# Sheet1.net
KiCad netlist of a schematic drawn in Altium Designer
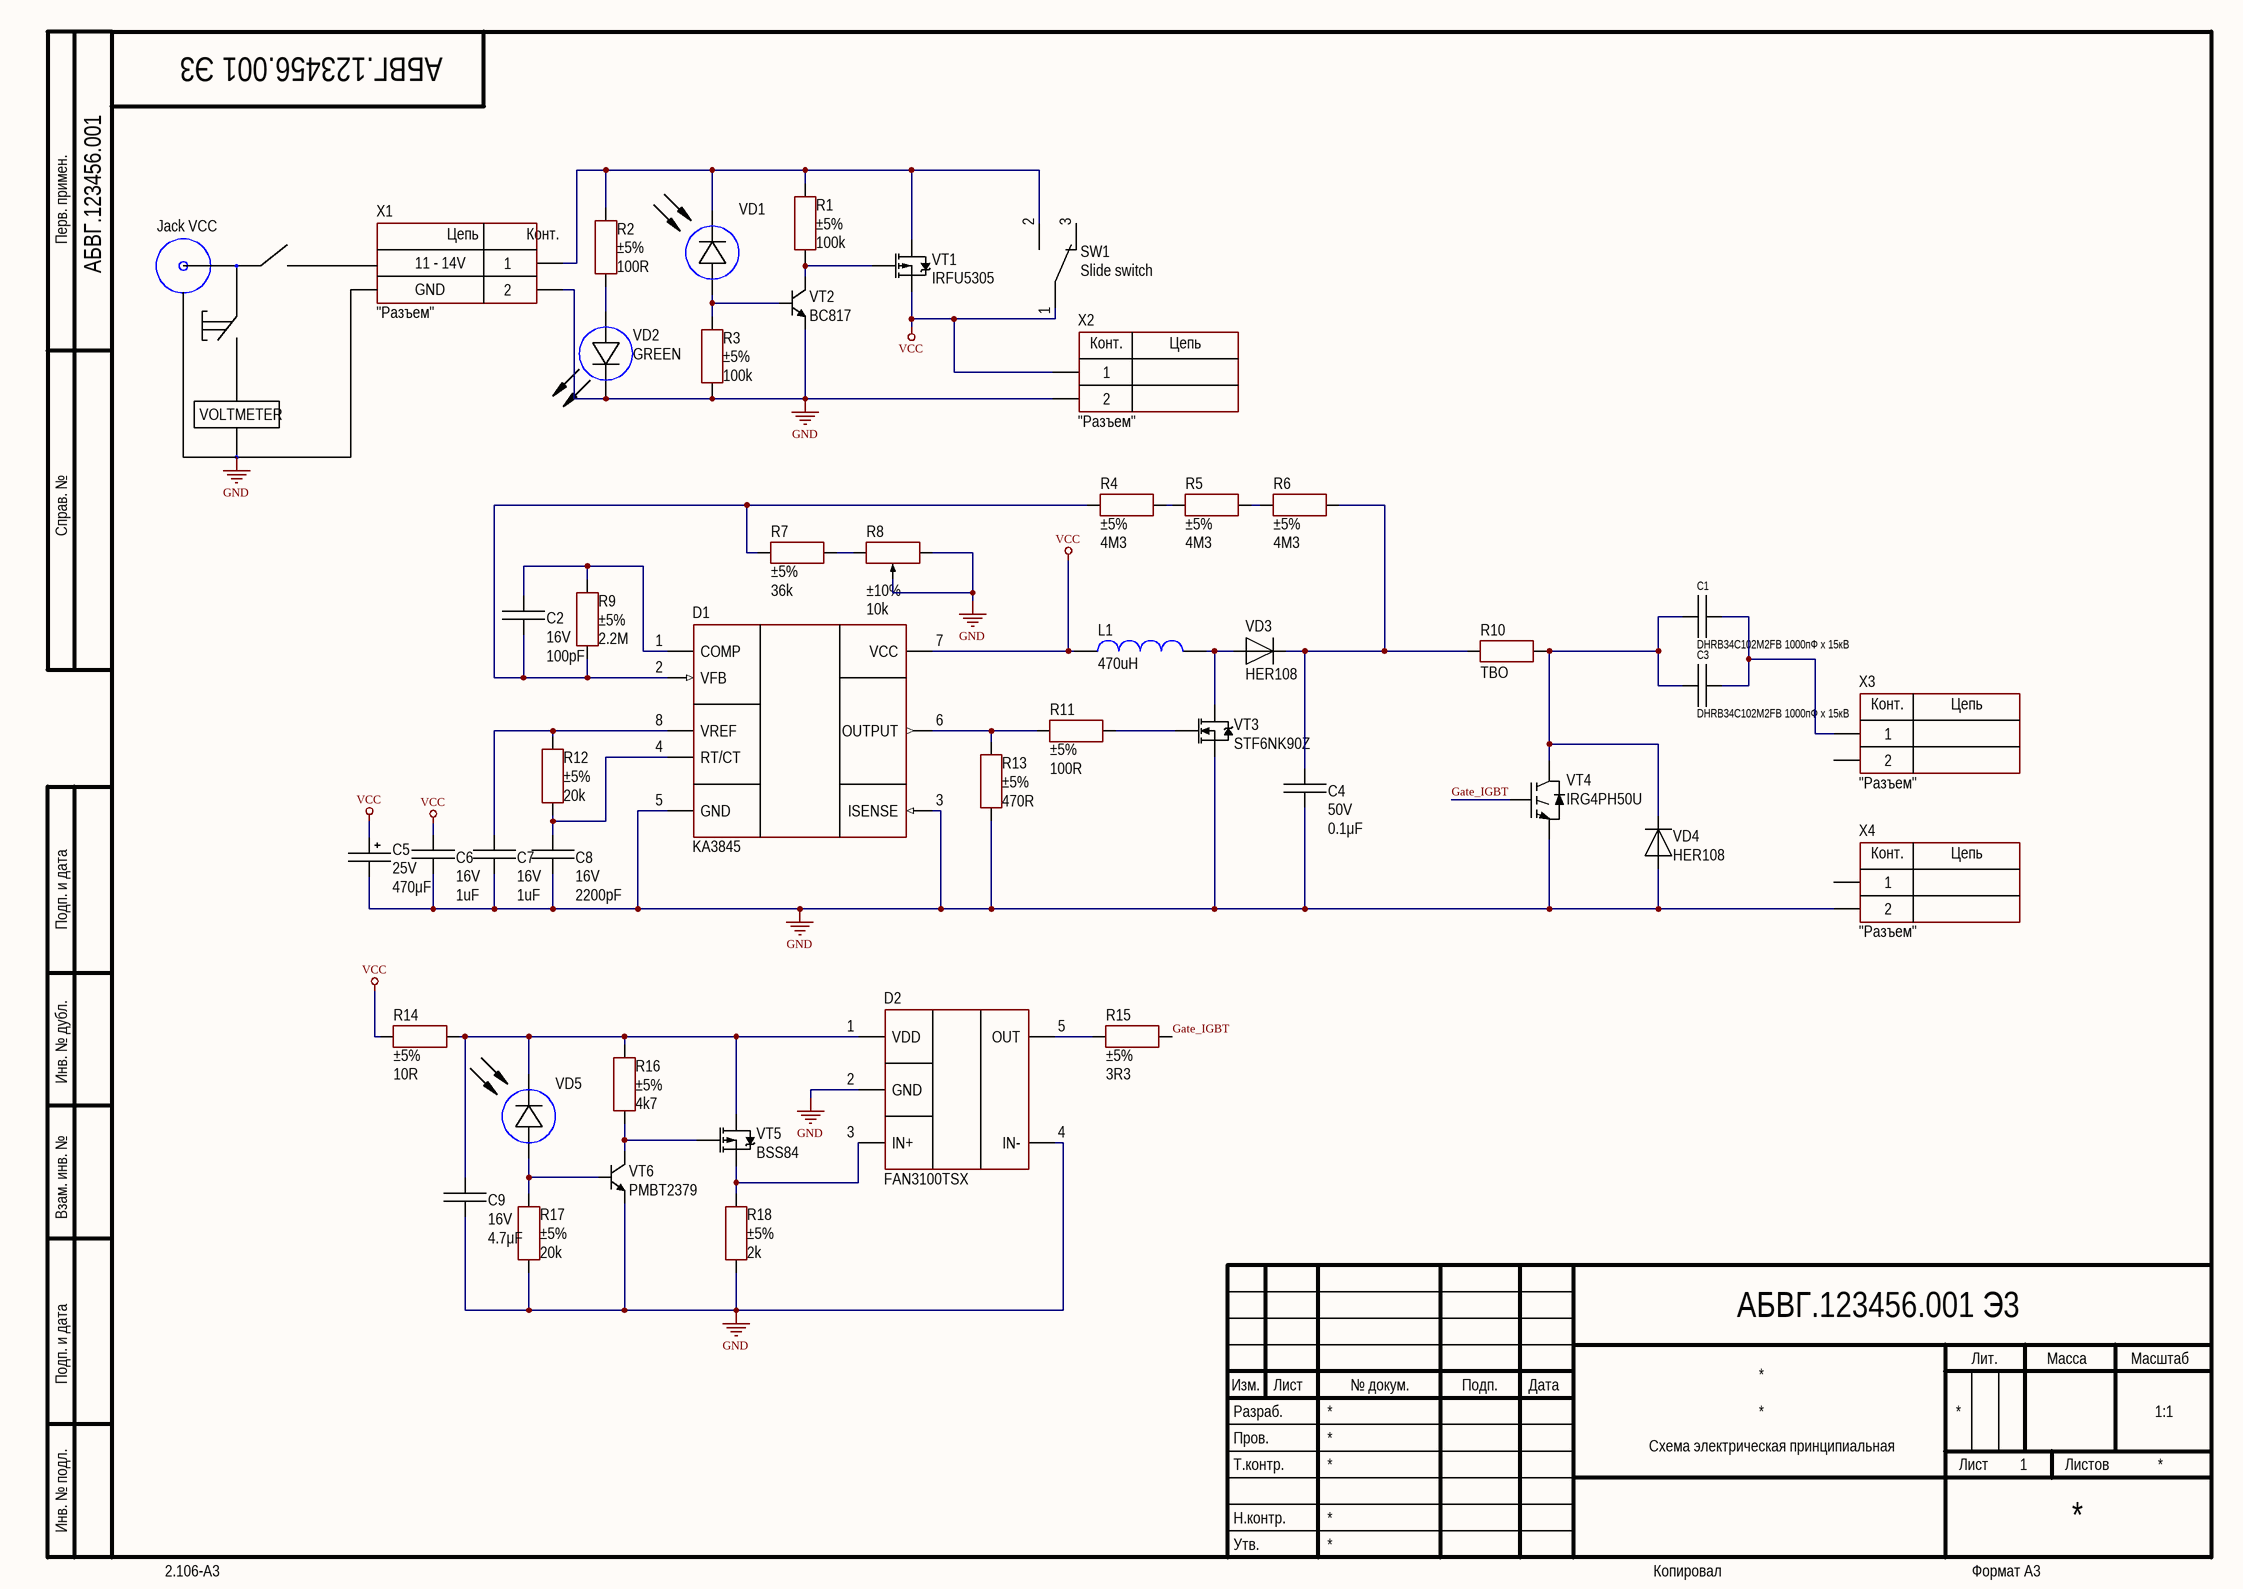
[diagram p0: Sheet1.SchDoc]

(export (version "E")
  (design (tool "Eeschema 10.0.6"))
  (components
    (comp (ref "C1")
      (value "DHRB34C102M2FB 1000пФ х 15кВ")
      (footprint "CAP: HV_CYL_METALL-PAPER_CAP")
      (libsource (lib "capacitor") (part "THROUGH_HOLE_CAP"))
    )
    (comp (ref "C2")
      (value "100pF")
      (footprint "CAP: 0805")
      (fields
        (field (name "MANUFACTURER") "Yageo")
        (field (name "PARTNUMBER") "CC0805KRX7R7BB104")
        (field (name "VALUEMANUFACTURERPARTNUMBER") "Ceramic capacitor, 100pF, X7R, ±10%, 16V, 0805, -55...+125°C")
        (field (name "VOLTAGE") "16V")
      )
      (libsource (lib "capacitor") (part "Ceramic_0805"))
    )
    (comp (ref "C3")
      (value "DHRB34C102M2FB 1000пФ х 15кВ")
      (footprint "CAP: HV_CYL_METALL-PAPER_CAP")
      (libsource (lib "capacitor") (part "THROUGH_HOLE_CAP"))
    )
    (comp (ref "C4")
      (value "0.1μF")
      (footprint "CAP: 2220")
      (fields
        (field (name "MANUFACTURER") "Yageo")
        (field (name "PARTNUMBER") "CC2220KKX7R9BB105")
        (field (name "VALUEMANUFACTURERPARTNUMBER") "Ceramic capacitor, 0.1μF, X7R, ±10%, 50V, 2220, -55...+125°C")
        (field (name "VOLTAGE") "50V")
      )
      (libsource (lib "capacitor") (part "Ceramic_2220"))
    )
    (comp (ref "C5")
      (value "470μF")
      (footprint "CAP: D8C3.5H12")
      (fields
        (field (name "MANUFACTURER") "Wurth")
        (field (name "PARTNUMBER") "860080475013")
        (field (name "VALUEMANUFACTURERPARTNUMBER") "Aluminium capacitor, 470μF, 25V, ±20%, 54mOhm, 14x10x5 mm, -55...+105°C")
        (field (name "VOLTAGE") "25V")
      )
      (libsource (lib "capacitor") (part "Aluminium"))
    )
    (comp (ref "C6")
      (value "1uF")
      (footprint "CAP: 0805")
      (fields
        (field (name "MANUFACTURER") "Yageo")
        (field (name "PARTNUMBER") "CC0805KRX7R7BB104")
        (field (name "VALUEMANUFACTURERPARTNUMBER") "Ceramic capacitor, 1uF, X7R, ±10%, 16V, 0805, -55...+125°C")
        (field (name "VOLTAGE") "16V")
      )
      (libsource (lib "capacitor") (part "Ceramic_0805"))
    )
    (comp (ref "C7")
      (value "1uF")
      (footprint "CAP: 0805")
      (fields
        (field (name "MANUFACTURER") "Yageo")
        (field (name "PARTNUMBER") "CC0805KRX7R7BB104")
        (field (name "VALUEMANUFACTURERPARTNUMBER") "Ceramic capacitor, 1uF, X7R, ±10%, 16V, 0805, -55...+125°C")
        (field (name "VOLTAGE") "16V")
      )
      (libsource (lib "capacitor") (part "Ceramic_0805"))
    )
    (comp (ref "C8")
      (value "2200pF")
      (footprint "CAP: 0805")
      (fields
        (field (name "MANUFACTURER") "Yageo")
        (field (name "PARTNUMBER") "CC0805KRX7R7BB104")
        (field (name "VALUEMANUFACTURERPARTNUMBER") "Ceramic capacitor, 2200pF, X7R, ±10%, 16V, 0805, -55...+125°C")
        (field (name "VOLTAGE") "16V")
      )
      (libsource (lib "capacitor") (part "Ceramic_0805"))
    )
    (comp (ref "C9")
      (value "4.7μF")
      (footprint "CAP: 0805")
      (fields
        (field (name "MANUFACTURER") "Yageo")
        (field (name "PARTNUMBER") "CC0805KRX7R7BB104")
        (field (name "VALUEMANUFACTURERPARTNUMBER") "Ceramic capacitor, 4.7μF, X7R, ±10%, 16V, 0805, -55...+125°C")
        (field (name "VOLTAGE") "16V")
      )
      (libsource (lib "capacitor") (part "Ceramic_0805"))
    )
    (comp (ref "D1")
      (value "~")
      (footprint "8-SOIC")
      (description "PWM controller")
      (fields
        (field (name "MANUFACTURER") "ON Semiconductor")
        (field (name "VALUEMANUFACTURERPARTNUMBER") "PWM controller, supply 10...30V, 500kHz, External switch, -40...+105°C, 8-SOIC")
        (field (name "PARTNUMBER") "KA3845")
      )
      (libsource (lib "ic-power-supply") (part "UC3842BVD1R2G"))
    )
    (comp (ref "D2")
      (value "FAN3100TSX")
      (footprint "SOT23-5")
      (description "Gate driver")
      (libsource (lib "ic-gate-driver") (part "FAN3100TSX"))
    )
    (comp (ref "L1")
      (value "470uH")
      (footprint "IND: DUMBELL 8.5x11x5")
      (libsource (lib "inductor") (part "Inductor_dumbbell"))
    )
    (comp (ref "R1")
      (value "100k")
      (footprint "RES: 0805")
      (fields
        (field (name "MANUFACTURER") "Yageo")
        (field (name "PARTNUMBER") "RC0805JR-07100RL")
        (field (name "VALUEMANUFACTURERPARTNUMBER") "Resistor film, 100k, ±5%, 0805, 0.125W, -55...+125°C")
        (field (name "TOLERANCE") "±5%")
      )
      (libsource (lib "") (part "Resistor_0805_2"))
    )
    (comp (ref "R2")
      (value "100R")
      (footprint "RES: 0805")
      (fields
        (field (name "MANUFACTURER") "Yageo")
        (field (name "PARTNUMBER") "RC0805JR-07100RL")
        (field (name "VALUEMANUFACTURERPARTNUMBER") "Resistor film, 100R, ±5%, 0805, 0.125W, -55...+125°C")
        (field (name "TOLERANCE") "±5%")
      )
      (libsource (lib "") (part "Resistor_0805_4"))
    )
    (comp (ref "R3")
      (value "100k")
      (footprint "RES: 0805")
      (fields
        (field (name "MANUFACTURER") "Yageo")
        (field (name "PARTNUMBER") "RC0805JR-07100RL")
        (field (name "VALUEMANUFACTURERPARTNUMBER") "Resistor film, 100k, ±5%, 0805, 0.125W, -55...+125°C")
        (field (name "TOLERANCE") "±5%")
      )
      (libsource (lib "") (part "Resistor_0805_1"))
    )
    (comp (ref "R4")
      (value "4M3")
      (footprint "RES: 1206")
      (fields
        (field (name "MANUFACTURER") "Yageo")
        (field (name "PARTNUMBER") "RC1206JR-07100RL")
        (field (name "VALUEMANUFACTURERPARTNUMBER") "Resistor film, 4M3, ±5%, 1206, 0.25W, -55...+125°C")
        (field (name "TOLERANCE") "±5%")
      )
      (libsource (lib "resistor") (part "Resistor_1206"))
    )
    (comp (ref "R5")
      (value "4M3")
      (footprint "RES: 1206")
      (fields
        (field (name "MANUFACTURER") "Yageo")
        (field (name "PARTNUMBER") "RC1206JR-07100RL")
        (field (name "VALUEMANUFACTURERPARTNUMBER") "Resistor film, 4M3, ±5%, 1206, 0.25W, -55...+125°C")
        (field (name "TOLERANCE") "±5%")
      )
      (libsource (lib "resistor") (part "Resistor_1206"))
    )
    (comp (ref "R6")
      (value "4M3")
      (footprint "RES: 1206")
      (fields
        (field (name "MANUFACTURER") "Yageo")
        (field (name "PARTNUMBER") "RC1206JR-07100RL")
        (field (name "VALUEMANUFACTURERPARTNUMBER") "Resistor film, 4M3, ±5%, 1206, 0.25W, -55...+125°C")
        (field (name "TOLERANCE") "±5%")
      )
      (libsource (lib "resistor") (part "Resistor_1206"))
    )
    (comp (ref "R7")
      (value "36k")
      (footprint "RES: 0805")
      (fields
        (field (name "MANUFACTURER") "Yageo")
        (field (name "PARTNUMBER") "RC0805JR-07100RL")
        (field (name "VALUEMANUFACTURERPARTNUMBER") "Resistor film, 36k, ±5%, 0805, 0.125W, -55...+125°C")
        (field (name "TOLERANCE") "±5%")
      )
      (libsource (lib "") (part "Resistor_0805_3"))
    )
    (comp (ref "R8")
      (value "10k")
      (footprint "RES: 3362P")
      (fields
        (field (name "MANUFACTURER") "Bourns")
        (field (name "PARTNUMBER") "3296W-1-103LF")
        (field (name "VALUEMANUFACTURERPARTNUMBER") "Resistor film, 10k, ±10%, 3296W, 0.5W, -55...+125°C")
        (field (name "TOLERANCE") "±10%")
      )
      (libsource (lib "resistor") (part "Trimmer"))
    )
    (comp (ref "R9")
      (value "2.2M")
      (footprint "RES: 0805")
      (fields
        (field (name "MANUFACTURER") "Yageo")
        (field (name "PARTNUMBER") "RC0805JR-07100RL")
        (field (name "VALUEMANUFACTURERPARTNUMBER") "Resistor film, 2.2M, ±5%, 0805, 0.125W, -55...+125°C")
        (field (name "TOLERANCE") "±5%")
      )
      (libsource (lib "") (part "Resistor_0805_1"))
    )
    (comp (ref "R10")
      (value "ТВО")
      (footprint "RES: ТВО 0.5")
      (libsource (lib "resistor") (part "HV RESISTOR"))
    )
    (comp (ref "R11")
      (value "100R")
      (footprint "RES: 1206")
      (fields
        (field (name "MANUFACTURER") "Yageo")
        (field (name "PARTNUMBER") "RC1206JR-07100RL")
        (field (name "VALUEMANUFACTURERPARTNUMBER") "Resistor film, 100R, ±5%, 1206, 0.25W, -55...+125°C")
        (field (name "TOLERANCE") "±5%")
      )
      (libsource (lib "") (part "Resistor_1206_1"))
    )
    (comp (ref "R12")
      (value "20k")
      (footprint "RES: 0805")
      (fields
        (field (name "MANUFACTURER") "Yageo")
        (field (name "PARTNUMBER") "RC0805JR-07100RL")
        (field (name "VALUEMANUFACTURERPARTNUMBER") "Resistor film, 20k, ±5%, 0805, 0.125W, -55...+125°C")
        (field (name "TOLERANCE") "±5%")
      )
      (libsource (lib "") (part "Resistor_0805_1"))
    )
    (comp (ref "R13")
      (value "470R")
      (footprint "RES: 0805")
      (fields
        (field (name "MANUFACTURER") "Yageo")
        (field (name "PARTNUMBER") "RC0805JR-07100RL")
        (field (name "VALUEMANUFACTURERPARTNUMBER") "Resistor film, 470R, ±5%, 0805, 0.125W, -55...+125°C")
        (field (name "TOLERANCE") "±5%")
      )
      (libsource (lib "resistor") (part "Resistor_0805"))
    )
    (comp (ref "R14")
      (value "10R")
      (footprint "RES: 1206")
      (fields
        (field (name "MANUFACTURER") "Yageo")
        (field (name "PARTNUMBER") "RC1206JR-07100RL")
        (field (name "VALUEMANUFACTURERPARTNUMBER") "Resistor film, 10R, ±5%, 1206, 0.25W, -55...+125°C")
        (field (name "TOLERANCE") "±5%")
      )
      (libsource (lib "resistor") (part "Resistor_1206"))
    )
    (comp (ref "R15")
      (value "3R3")
      (footprint "RES: 1206")
      (fields
        (field (name "MANUFACTURER") "Yageo")
        (field (name "PARTNUMBER") "RC1206JR-07100RL")
        (field (name "VALUEMANUFACTURERPARTNUMBER") "Resistor film, 3R3, ±5%, 1206, 0.25W, -55...+125°C")
        (field (name "TOLERANCE") "±5%")
      )
      (libsource (lib "resistor") (part "Resistor_1206"))
    )
    (comp (ref "R16")
      (value "4k7")
      (footprint "RES: 0805")
      (fields
        (field (name "MANUFACTURER") "Yageo")
        (field (name "PARTNUMBER") "RC0805JR-07100RL")
        (field (name "VALUEMANUFACTURERPARTNUMBER") "Resistor film, 4k7, ±5%, 0805, 0.125W, -55...+125°C")
        (field (name "TOLERANCE") "±5%")
      )
      (libsource (lib "resistor") (part "Resistor_0805"))
    )
    (comp (ref "R17")
      (value "20k")
      (footprint "RES: 0805")
      (fields
        (field (name "MANUFACTURER") "Yageo")
        (field (name "PARTNUMBER") "RC0805JR-07100RL")
        (field (name "VALUEMANUFACTURERPARTNUMBER") "Resistor film, 20k, ±5%, 0805, 0.125W, -55...+125°C")
        (field (name "TOLERANCE") "±5%")
      )
      (libsource (lib "resistor") (part "Resistor_0805"))
    )
    (comp (ref "R18")
      (value "2k")
      (footprint "RES: 0805")
      (fields
        (field (name "MANUFACTURER") "Yageo")
        (field (name "PARTNUMBER") "RC0805JR-07100RL")
        (field (name "VALUEMANUFACTURERPARTNUMBER") "Resistor film, 2k, ±5%, 0805, 0.125W, -55...+125°C")
        (field (name "TOLERANCE") "±5%")
      )
      (libsource (lib "resistor") (part "Resistor_0805"))
    )
    (comp (ref "SW1")
      (value "Slide switch")
      (footprint "SW: Slide_switch 3mm between outputs")
      (libsource (lib "electromechanics") (part "Slide_switch"))
    )
    (comp (ref "VD1") (value "SHF250") (footprint "LED: SFH757") (libsource (lib "") (part "SHF250_1")))
    (comp (ref "VD2")
      (value "~")
      (footprint "through component 5 mm")
      (fields
        (field (name "VALUEMANUFACTURERPARTNUMBER") "LED, Green, *, *, *, -55...+150°C")
        (field (name "COLOR") "GREEN")
      )
      (libsource (lib "diode") (part "LED_single"))
    )
    (comp (ref "VD3")
      (value "HER108")
      (footprint "DIODE: DO-41")
      (libsource (lib "diode") (part "Through_hole_single_diode"))
    )
    (comp (ref "VD4")
      (value "HER108")
      (footprint "DIODE: DO-41")
      (libsource (lib "diode") (part "Through_hole_single_diode"))
    )
    (comp (ref "VD5") (value "SHF250") (footprint "LED: SFH757") (libsource (lib "diode") (part "SHF250")))
    (comp (ref "VT1")
      (value "~")
      (footprint "DPAK")
      (fields
        (field (name "MANUFACTURER") "Infineon Technologies")
        (field (name "VALUEMANUFACTURERPARTNUMBER") "MOSFET P-channel transistor, 20V, 2.6A, 2.9nC, 2.5W, 135mOhm, 220pF, SOT-23, -55...+150°C")
        (field (name "PARTNUMBER") "IRFU5305")
      )
      (libsource (lib "transistor") (part "MOSFET_P_132"))
    )
    (comp (ref "VT2")
      (value "~")
      (footprint "SOT23")
      (fields
        (field (name "MANUFACTURER") "ON Semiconductor")
        (field (name "VALUEMANUFACTURERPARTNUMBER") "NPN transistor, 45V, 100mA, 100MHz, 300mW, 0.6V, 420, SOT-23, -55...+125°C")
        (field (name "PARTNUMBER") "BC817")
      )
      (libsource (lib "transistor") (part "BJT_NPN_132"))
    )
    (comp (ref "VT3")
      (value "~")
      (footprint "TO-220 HV")
      (fields
        (field (name "MANUFACTURER") "Infineon Technologies")
        (field (name "VALUEMANUFACTURERPARTNUMBER") "MOSFET N-channel transistor, 80V, 7A, 9.1nC, 2.5W, 34mOhm, 756pF, 8-TDSON, -55...+150°C")
        (field (name "PARTNUMBER") "STF6NK90Z")
      )
      (libsource (lib "transistor") (part "MOSFET_N_123"))
    )
    (comp (ref "VT4")
      (value "~")
      (footprint "TO247")
      (fields
        (field (name "MANUFACTURER") "Rohm Semiconductor")
        (field (name "VALUEMANUFACTURERPARTNUMBER") "IGBT transistor, 650V, 40A, 40nC, 144W, 2.1V, 22ns/73ns, TO247, -55...+125°C")
        (field (name "PARTNUMBER") "IRG4PH50U")
      )
      (libsource (lib "transistor") (part "IGBT"))
    )
    (comp (ref "VT5")
      (value "~")
      (footprint "SOT23")
      (fields
        (field (name "MANUFACTURER") "Infineon Technologies")
        (field (name "VALUEMANUFACTURERPARTNUMBER") "MOSFET P-channel transistor, 20V, 2.6A, 2.9nC, 2.5W, 135mOhm, 220pF, SOT-23, -55...+150°C")
        (field (name "PARTNUMBER") "BSS84")
      )
      (libsource (lib "transistor") (part "MOSFET_P_132"))
    )
    (comp (ref "VT6")
      (value "~")
      (footprint "SOT23")
      (fields
        (field (name "MANUFACTURER") "ON Semiconductor")
        (field (name "VALUEMANUFACTURERPARTNUMBER") "NPN transistor, 45V, 100mA, 100MHz, 300mW, 0.6V, 420, SOT-23, -55...+125°C")
        (field (name "PARTNUMBER") "PMBT2379")
      )
      (libsource (lib "transistor") (part "BJT_NPN_132"))
    )
    (comp (ref "X1")
      (value "~")
      (footprint "CON: KF301-5.0-2P")
      (fields
        (field (name "MANUFACTURER") "Degson")
        (field (name "VALUEMANUFACTURERPARTNUMBER") "Terminal connector, 2pin, 3.5mm, 300VAC, 10A")
        (field (name "PARTNUMBER") "DG350-3.5-02P-14")
        (field (name "COMMENTTEXT") "\"Разъем\"")
      )
      (libsource (lib "") (part "Connector_terminal_2pin_1"))
    )
    (comp (ref "X2")
      (value "~")
      (footprint "CON: KF301-5.0-2P")
      (fields
        (field (name "MANUFACTURER") "Degson")
        (field (name "VALUEMANUFACTURERPARTNUMBER") "Terminal connector, 2pin, 3.5mm, 300VAC, 10A")
        (field (name "PARTNUMBER") "DG350-3.5-02P-14")
        (field (name "COMMENTTEXT") "\"Разъем\"")
      )
      (libsource (lib "connector") (part "Connector_terminal_2pin"))
    )
    (comp (ref "X3")
      (value "~")
      (footprint "CON: KF301-5.0-2P")
      (fields
        (field (name "MANUFACTURER") "Degson")
        (field (name "VALUEMANUFACTURERPARTNUMBER") "Terminal connector, 2pin, 3.5mm, 300VAC, 10A")
        (field (name "PARTNUMBER") "DG350-3.5-02P-14")
        (field (name "COMMENTTEXT") "\"Разъем\"")
      )
      (libsource (lib "connector") (part "Connector_terminal_2pin"))
    )
    (comp (ref "X4")
      (value "~")
      (footprint "CON: KF301-5.0-2P")
      (fields
        (field (name "MANUFACTURER") "Degson")
        (field (name "VALUEMANUFACTURERPARTNUMBER") "Terminal connector, 2pin, 3.5mm, 300VAC, 10A")
        (field (name "PARTNUMBER") "DG350-3.5-02P-14")
        (field (name "COMMENTTEXT") "\"Разъем\"")
      )
      (libsource (lib "connector") (part "Connector_terminal_2pin"))
    )
  )
  (nets
    (net (code "1") (name "/Gate_IGBT") (class "Default")
      (node (ref "R15") (pin "2") (pinfunction "2_2") (pintype "passive"))
      (node (ref "VT4") (pin "1") (pinfunction "G_1") (pintype "passive"))
    )
    (net (code "2") (name "GND") (class "Default")
      (node (ref "C4") (pin "1") (pinfunction "1_1") (pintype "passive"))
      (node (ref "C5") (pin "2") (pinfunction "2_2") (pintype "passive"))
      (node (ref "C6") (pin "1") (pinfunction "1_1") (pintype "passive"))
      (node (ref "C7") (pin "1") (pinfunction "1_1") (pintype "passive"))
      (node (ref "C8") (pin "1") (pinfunction "1_1") (pintype "passive"))
      (node (ref "C9") (pin "1") (pinfunction "1_1") (pintype "passive"))
      (node (ref "D1") (pin "3") (pinfunction "ISENSE_3") (pintype "input"))
      (node (ref "D1") (pin "5") (pinfunction "GND_5") (pintype "passive"))
      (node (ref "D2") (pin "2") (pinfunction "GND_2") (pintype "passive"))
      (node (ref "D2") (pin "4") (pinfunction "IN-_4") (pintype "passive"))
      (node (ref "R13") (pin "2") (pinfunction "2_2") (pintype "passive"))
      (node (ref "R17") (pin "2") (pinfunction "2_2") (pintype "passive"))
      (node (ref "R18") (pin "2") (pinfunction "2_2") (pintype "passive"))
      (node (ref "R3") (pin "1") (pinfunction "1_1") (pintype "passive"))
      (node (ref "R8") (pin "1") (pinfunction "1_1") (pintype "passive"))
      (node (ref "R8") (pin "2") (pinfunction "2_2") (pintype "passive"))
      (node (ref "VD2") (pin "2") (pinfunction "C_2") (pintype "passive"))
      (node (ref "VD4") (pin "1") (pinfunction "1_1") (pintype "passive"))
      (node (ref "VT2") (pin "2") (pinfunction "E_2") (pintype "passive"))
      (node (ref "VT3") (pin "3") (pinfunction "S_3") (pintype "passive"))
      (node (ref "VT4") (pin "3") (pinfunction "E_3") (pintype "passive"))
      (node (ref "VT6") (pin "2") (pinfunction "E_2") (pintype "passive"))
      (node (ref "X1") (pin "2") (pinfunction "2_2") (pintype "passive"))
      (node (ref "X2") (pin "2") (pinfunction "2_2") (pintype "passive"))
      (node (ref "X4") (pin "2") (pinfunction "2_2") (pintype "passive"))
    )
    (net (code "3") (name "Net-(C1-Pad1)") (class "Default")
      (node (ref "C1") (pin "1") (pinfunction "1_1") (pintype "passive"))
      (node (ref "C3") (pin "1") (pinfunction "1_1") (pintype "passive"))
      (node (ref "X3") (pin "1") (pinfunction "1_1") (pintype "passive"))
    )
    (net (code "4") (name "Net-(C4-Pad2)") (class "Default")
      (node (ref "C4") (pin "2") (pinfunction "2_2") (pintype "passive"))
      (node (ref "R10") (pin "1") (pinfunction "1_1") (pintype "passive"))
      (node (ref "R6") (pin "2") (pinfunction "2_2") (pintype "passive"))
      (node (ref "VD3") (pin "2") (pinfunction "2_2") (pintype "passive"))
    )
    (net (code "5") (name "Net-(D1-COMP)") (class "Default")
      (node (ref "C2") (pin "2") (pinfunction "2_2") (pintype "passive"))
      (node (ref "D1") (pin "1") (pinfunction "COMP_1") (pintype "passive"))
      (node (ref "R9") (pin "2") (pinfunction "2_2") (pintype "passive"))
    )
    (net (code "6") (name "Net-(D1-OUTPUT)") (class "Default")
      (node (ref "D1") (pin "6") (pinfunction "OUTPUT_6") (pintype "output"))
      (node (ref "R11") (pin "2") (pinfunction "2_2") (pintype "passive"))
      (node (ref "R13") (pin "1") (pinfunction "1_1") (pintype "passive"))
    )
    (net (code "7") (name "Net-(D1-RT{slash}CT)") (class "Default")
      (node (ref "C8") (pin "2") (pinfunction "2_2") (pintype "passive"))
      (node (ref "D1") (pin "4") (pinfunction "RT/CT_4") (pintype "passive"))
      (node (ref "R12") (pin "1") (pinfunction "1_1") (pintype "passive"))
    )
    (net (code "8") (name "Net-(D1-VFB)") (class "Default")
      (node (ref "C2") (pin "1") (pinfunction "1_1") (pintype "passive"))
      (node (ref "D1") (pin "2") (pinfunction "VFB_2") (pintype "input"))
      (node (ref "R4") (pin "1") (pinfunction "1_1") (pintype "passive"))
      (node (ref "R7") (pin "2") (pinfunction "2_2") (pintype "passive"))
      (node (ref "R9") (pin "1") (pinfunction "1_1") (pintype "passive"))
    )
    (net (code "9") (name "Net-(D1-VREF)") (class "Default")
      (node (ref "C7") (pin "2") (pinfunction "2_2") (pintype "passive"))
      (node (ref "D1") (pin "8") (pinfunction "VREF_8") (pintype "passive"))
      (node (ref "R12") (pin "2") (pinfunction "2_2") (pintype "passive"))
    )
    (net (code "10") (name "Net-(D2-IN+)") (class "Default")
      (node (ref "D2") (pin "3") (pinfunction "IN+_3") (pintype "passive"))
      (node (ref "R18") (pin "1") (pinfunction "1_1") (pintype "passive"))
      (node (ref "VT5") (pin "2") (pinfunction "S_2") (pintype "passive"))
    )
    (net (code "11") (name "Net-(D2-OUT)") (class "Default")
      (node (ref "D2") (pin "5") (pinfunction "OUT_5") (pintype "passive"))
      (node (ref "R15") (pin "1") (pinfunction "1_1") (pintype "passive"))
    )
    (net (code "12") (name "Net-(D2-VDD)") (class "Default")
      (node (ref "C9") (pin "2") (pinfunction "2_2") (pintype "passive"))
      (node (ref "D2") (pin "1") (pinfunction "VDD_1") (pintype "passive"))
      (node (ref "R14") (pin "2") (pinfunction "2_2") (pintype "passive"))
      (node (ref "R16") (pin "1") (pinfunction "1_1") (pintype "passive"))
      (node (ref "VD5") (pin "2") (pinfunction "C_2") (pintype "passive"))
      (node (ref "VT5") (pin "3") (pinfunction "D_3") (pintype "passive"))
    )
    (net (code "13") (name "Net-(R4-Pad2)") (class "Default")
      (node (ref "R4") (pin "2") (pinfunction "2_2") (pintype "passive"))
      (node (ref "R5") (pin "1") (pinfunction "1_1") (pintype "passive"))
    )
    (net (code "14") (name "Net-(R5-Pad2)") (class "Default")
      (node (ref "R5") (pin "2") (pinfunction "2_2") (pintype "passive"))
      (node (ref "R6") (pin "1") (pinfunction "1_1") (pintype "passive"))
    )
    (net (code "15") (name "Net-(R7-Pad1)") (class "Default")
      (node (ref "R7") (pin "1") (pinfunction "1_1") (pintype "passive"))
      (node (ref "R8") (pin "3") (pinfunction "3_3") (pintype "passive"))
    )
    (net (code "16") (name "Net-(VD1-A)") (class "Default")
      (node (ref "R3") (pin "2") (pinfunction "2_2") (pintype "passive"))
      (node (ref "VD1") (pin "1") (pinfunction "A_1") (pintype "passive"))
      (node (ref "VT2") (pin "1") (pinfunction "B_1") (pintype "passive"))
    )
    (net (code "17") (name "Net-(VD1-C)") (class "Default")
      (node (ref "R1") (pin "2") (pinfunction "2_2") (pintype "passive"))
      (node (ref "R2") (pin "2") (pinfunction "2_2") (pintype "passive"))
      (node (ref "SW1") (pin "2") (pinfunction "4_2") (pintype "passive"))
      (node (ref "VD1") (pin "2") (pinfunction "C_2") (pintype "passive"))
      (node (ref "VT1") (pin "3") (pinfunction "D_3") (pintype "passive"))
      (node (ref "X1") (pin "1") (pinfunction "1_1") (pintype "passive"))
    )
    (net (code "18") (name "Net-(VD2-A)") (class "Default")
      (node (ref "R2") (pin "1") (pinfunction "1_1") (pintype "passive"))
      (node (ref "VD2") (pin "1") (pinfunction "A_1") (pintype "passive"))
    )
    (net (code "19") (name "Net-(VD5-A)") (class "Default")
      (node (ref "R17") (pin "1") (pinfunction "1_1") (pintype "passive"))
      (node (ref "VD5") (pin "1") (pinfunction "A_1") (pintype "passive"))
      (node (ref "VT6") (pin "1") (pinfunction "B_1") (pintype "passive"))
    )
    (net (code "20") (name "Net-(VT1-G)") (class "Default")
      (node (ref "R1") (pin "1") (pinfunction "1_1") (pintype "passive"))
      (node (ref "VT1") (pin "1") (pinfunction "G_1") (pintype "passive"))
      (node (ref "VT2") (pin "3") (pinfunction "C_3") (pintype "passive"))
    )
    (net (code "21") (name "Net-(VT3-D)") (class "Default")
      (node (ref "L1") (pin "1") (pinfunction "1_1") (pintype "passive"))
      (node (ref "VD3") (pin "1") (pinfunction "1_1") (pintype "passive"))
      (node (ref "VT3") (pin "2") (pinfunction "D_2") (pintype "passive"))
    )
    (net (code "22") (name "Net-(VT3-G)") (class "Default")
      (node (ref "R11") (pin "1") (pinfunction "1_1") (pintype "passive"))
      (node (ref "VT3") (pin "1") (pinfunction "G_1") (pintype "passive"))
    )
    (net (code "23") (name "Net-(VT4-C)") (class "Default")
      (node (ref "C1") (pin "2") (pinfunction "2_2") (pintype "passive"))
      (node (ref "C3") (pin "2") (pinfunction "2_2") (pintype "passive"))
      (node (ref "R10") (pin "2") (pinfunction "2_2") (pintype "passive"))
      (node (ref "VD4") (pin "2") (pinfunction "2_2") (pintype "passive"))
      (node (ref "VT4") (pin "2") (pinfunction "C_2") (pintype "passive"))
    )
    (net (code "24") (name "Net-(VT5-G)") (class "Default")
      (node (ref "R16") (pin "2") (pinfunction "2_2") (pintype "passive"))
      (node (ref "VT5") (pin "1") (pinfunction "G_1") (pintype "passive"))
      (node (ref "VT6") (pin "3") (pinfunction "C_3") (pintype "passive"))
    )
    (net (code "25") (name "VCC") (class "Default")
      (node (ref "C5") (pin "1") (pinfunction "1_1") (pintype "passive"))
      (node (ref "C6") (pin "2") (pinfunction "2_2") (pintype "passive"))
      (node (ref "D1") (pin "7") (pinfunction "VCC_7") (pintype "passive"))
      (node (ref "L1") (pin "2") (pinfunction "2_2") (pintype "passive"))
      (node (ref "R14") (pin "1") (pinfunction "1_1") (pintype "passive"))
      (node (ref "SW1") (pin "1") (pinfunction "3_1") (pintype "passive"))
      (node (ref "VT1") (pin "2") (pinfunction "S_2") (pintype "passive"))
      (node (ref "X2") (pin "1") (pinfunction "1_1") (pintype "passive"))
    )
    (net (code "26") (name "unconnected-(SW1-4-Pad3)") (class "Default")
      (node (ref "SW1") (pin "3") (pinfunction "4_3") (pintype "passive"))
    )
    (net (code "27") (name "unconnected-(X3-Pad2)") (class "Default")
      (node (ref "X3") (pin "2") (pinfunction "2_2") (pintype "passive"))
    )
    (net (code "28") (name "unconnected-(X4-Pad1)") (class "Default")
      (node (ref "X4") (pin "1") (pinfunction "1_1") (pintype "passive"))
    )
  )
)
